# DC_POWER_SUPPLY.net
KiCad netlist of a schematic drawn in EAGLE
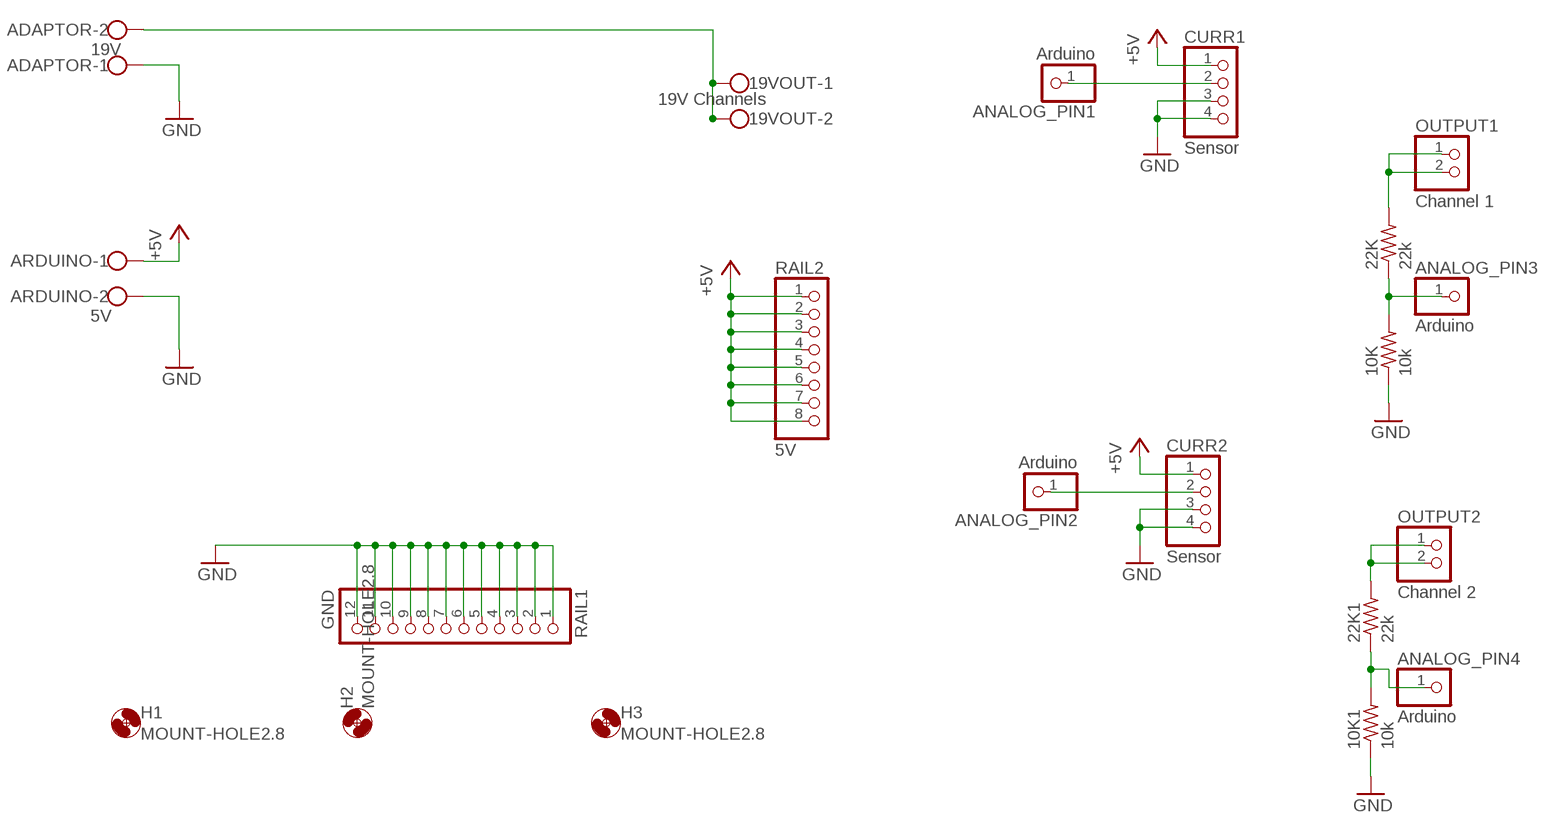
[diagram p0: schematic, sheet 1]

(export (version "E")
  (design (tool "Eeschema 10.0.6"))
  (components
    (comp (ref "10K")
      (value "10k")
      (footprint "eagle-import:0204_7")
      (libsource (lib "eagle-import") (part "R-US_0204/7"))
    )
    (comp (ref "10K1")
      (value "10k")
      (footprint "eagle-import:0204_7")
      (libsource (lib "eagle-import") (part "R-US_0204/7"))
    )
    (comp (ref "19VOUT")
      (value "19V Channels")
      (footprint "eagle-import:W237-102")
      (fields (field (name "MPN") "237-102"))
      (libsource (lib "eagle-import") (part "W237-102"))
    )
    (comp (ref "22K")
      (value "22k")
      (footprint "eagle-import:0207_7")
      (libsource (lib "eagle-import") (part "R-US_0207/7"))
    )
    (comp (ref "22K1")
      (value "22k")
      (footprint "eagle-import:0204_7")
      (libsource (lib "eagle-import") (part "R-US_0204/7"))
    )
    (comp (ref "ADAPTOR")
      (value "19V")
      (footprint "eagle-import:W237-102")
      (fields (field (name "MPN") "237-102"))
      (libsource (lib "eagle-import") (part "W237-102"))
    )
    (comp (ref "ANALOG_PIN1")
      (value "Arduino")
      (footprint "eagle-import:1X01")
      (libsource (lib "eagle-import") (part "PINHD-1X1"))
    )
    (comp (ref "ANALOG_PIN2")
      (value "Arduino")
      (footprint "eagle-import:1X01")
      (libsource (lib "eagle-import") (part "PINHD-1X1"))
    )
    (comp (ref "ANALOG_PIN3")
      (value "Arduino")
      (footprint "eagle-import:1X01")
      (libsource (lib "eagle-import") (part "PINHD-1X1"))
    )
    (comp (ref "ANALOG_PIN4")
      (value "Arduino")
      (footprint "eagle-import:1X01")
      (libsource (lib "eagle-import") (part "PINHD-1X1"))
    )
    (comp (ref "ARDUINO")
      (value "5V")
      (footprint "eagle-import:W237-102")
      (fields (field (name "MPN") "237-102"))
      (libsource (lib "eagle-import") (part "W237-102"))
    )
    (comp (ref "CURR1")
      (value "Sensor")
      (footprint "eagle-import:1X04")
      (libsource (lib "eagle-import") (part "PINHD-1X4"))
    )
    (comp (ref "CURR2")
      (value "Sensor")
      (footprint "eagle-import:1X04")
      (libsource (lib "eagle-import") (part "PINHD-1X4"))
    )
    (comp (ref "H1")
      (value "MOUNT-HOLE2.8")
      (footprint "eagle-import:2,8")
      (libsource (lib "eagle-import") (part "MOUNT-HOLE2.8"))
    )
    (comp (ref "H2")
      (value "MOUNT-HOLE2.8")
      (footprint "eagle-import:2,8")
      (libsource (lib "eagle-import") (part "MOUNT-HOLE2.8"))
    )
    (comp (ref "H3")
      (value "MOUNT-HOLE2.8")
      (footprint "eagle-import:2,8")
      (libsource (lib "eagle-import") (part "MOUNT-HOLE2.8"))
    )
    (comp (ref "OUTPUT1")
      (value "Channel 1")
      (footprint "eagle-import:1X02")
      (libsource (lib "eagle-import") (part "PINHD-1X2"))
    )
    (comp (ref "OUTPUT2")
      (value "Channel 2")
      (footprint "eagle-import:1X02")
      (libsource (lib "eagle-import") (part "PINHD-1X2"))
    )
    (comp (ref "RAIL1")
      (value "GND")
      (footprint "eagle-import:1X12")
      (libsource (lib "eagle-import") (part "PINHD-1X12"))
    )
    (comp (ref "RAIL2")
      (value "5V")
      (footprint "eagle-import:1X08")
      (libsource (lib "eagle-import") (part "PINHD-1X8"))
    )
  )
  (nets
    (net (code "1") (name "+5V") (class "Default")
      (node (ref "ARDUINO") (pin "1") (pinfunction "KL_1") (pintype "passive"))
      (node (ref "CURR1") (pin "1") (pinfunction "1_1") (pintype "passive"))
      (node (ref "CURR2") (pin "1") (pinfunction "1_1") (pintype "passive"))
      (node (ref "RAIL2") (pin "1") (pinfunction "1_1") (pintype "passive"))
      (node (ref "RAIL2") (pin "2") (pinfunction "2_2") (pintype "passive"))
      (node (ref "RAIL2") (pin "3") (pinfunction "3_3") (pintype "passive"))
      (node (ref "RAIL2") (pin "4") (pinfunction "4_4") (pintype "passive"))
      (node (ref "RAIL2") (pin "5") (pinfunction "5_5") (pintype "passive"))
      (node (ref "RAIL2") (pin "6") (pinfunction "6_6") (pintype "passive"))
      (node (ref "RAIL2") (pin "7") (pinfunction "7_7") (pintype "passive"))
      (node (ref "RAIL2") (pin "8") (pinfunction "8_8") (pintype "passive"))
    )
    (net (code "2") (name "GND") (class "Default")
      (node (ref "10K") (pin "1") (pinfunction "1_1") (pintype "passive"))
      (node (ref "10K1") (pin "1") (pinfunction "1_1") (pintype "passive"))
      (node (ref "ADAPTOR") (pin "1") (pinfunction "KL_1") (pintype "passive"))
      (node (ref "ARDUINO") (pin "2") (pinfunction "KL_2") (pintype "passive"))
      (node (ref "CURR1") (pin "3") (pinfunction "3_3") (pintype "passive"))
      (node (ref "CURR1") (pin "4") (pinfunction "4_4") (pintype "passive"))
      (node (ref "CURR2") (pin "3") (pinfunction "3_3") (pintype "passive"))
      (node (ref "CURR2") (pin "4") (pinfunction "4_4") (pintype "passive"))
      (node (ref "RAIL1") (pin "1") (pinfunction "1_1") (pintype "passive"))
      (node (ref "RAIL1") (pin "10") (pinfunction "10_10") (pintype "passive"))
      (node (ref "RAIL1") (pin "11") (pinfunction "11_11") (pintype "passive"))
      (node (ref "RAIL1") (pin "12") (pinfunction "12_12") (pintype "passive"))
      (node (ref "RAIL1") (pin "2") (pinfunction "2_2") (pintype "passive"))
      (node (ref "RAIL1") (pin "3") (pinfunction "3_3") (pintype "passive"))
      (node (ref "RAIL1") (pin "4") (pinfunction "4_4") (pintype "passive"))
      (node (ref "RAIL1") (pin "5") (pinfunction "5_5") (pintype "passive"))
      (node (ref "RAIL1") (pin "6") (pinfunction "6_6") (pintype "passive"))
      (node (ref "RAIL1") (pin "7") (pinfunction "7_7") (pintype "passive"))
      (node (ref "RAIL1") (pin "8") (pinfunction "8_8") (pintype "passive"))
      (node (ref "RAIL1") (pin "9") (pinfunction "9_9") (pintype "passive"))
    )
    (net (code "3") (name "Net-(10K-Pad2)") (class "Default")
      (node (ref "10K") (pin "2") (pinfunction "2_2") (pintype "passive"))
      (node (ref "22K") (pin "1") (pinfunction "1_1") (pintype "passive"))
      (node (ref "ANALOG_PIN3") (pin "1") (pinfunction "1_1") (pintype "passive"))
    )
    (net (code "4") (name "Net-(10K1-Pad2)") (class "Default")
      (node (ref "10K1") (pin "2") (pinfunction "2_2") (pintype "passive"))
      (node (ref "22K1") (pin "1") (pinfunction "1_1") (pintype "passive"))
      (node (ref "ANALOG_PIN4") (pin "1") (pinfunction "1_1") (pintype "passive"))
    )
    (net (code "5") (name "Net-(19VOUTA-KL)") (class "Default")
      (node (ref "19VOUT") (pin "1") (pinfunction "KL_1") (pintype "passive"))
      (node (ref "19VOUT") (pin "2") (pinfunction "KL_2") (pintype "passive"))
      (node (ref "ADAPTOR") (pin "2") (pinfunction "KL_2") (pintype "passive"))
    )
    (net (code "6") (name "Net-(22K-Pad2)") (class "Default")
      (node (ref "22K") (pin "2") (pinfunction "2_2") (pintype "passive"))
      (node (ref "OUTPUT1") (pin "1") (pinfunction "1_1") (pintype "passive"))
      (node (ref "OUTPUT1") (pin "2") (pinfunction "2_2") (pintype "passive"))
    )
    (net (code "7") (name "Net-(22K1-Pad2)") (class "Default")
      (node (ref "22K1") (pin "2") (pinfunction "2_2") (pintype "passive"))
      (node (ref "OUTPUT2") (pin "1") (pinfunction "1_1") (pintype "passive"))
      (node (ref "OUTPUT2") (pin "2") (pinfunction "2_2") (pintype "passive"))
    )
    (net (code "8") (name "Net-(ANALOG_PIN1-Pad1)") (class "Default")
      (node (ref "ANALOG_PIN1") (pin "1") (pinfunction "1_1") (pintype "passive"))
      (node (ref "CURR1") (pin "2") (pinfunction "2_2") (pintype "passive"))
    )
    (net (code "9") (name "Net-(ANALOG_PIN2-Pad1)") (class "Default")
      (node (ref "ANALOG_PIN2") (pin "1") (pinfunction "1_1") (pintype "passive"))
      (node (ref "CURR2") (pin "2") (pinfunction "2_2") (pintype "passive"))
    )
  )
)
